# LowLevelv3.net
KiCad netlist of a schematic drawn in EAGLE
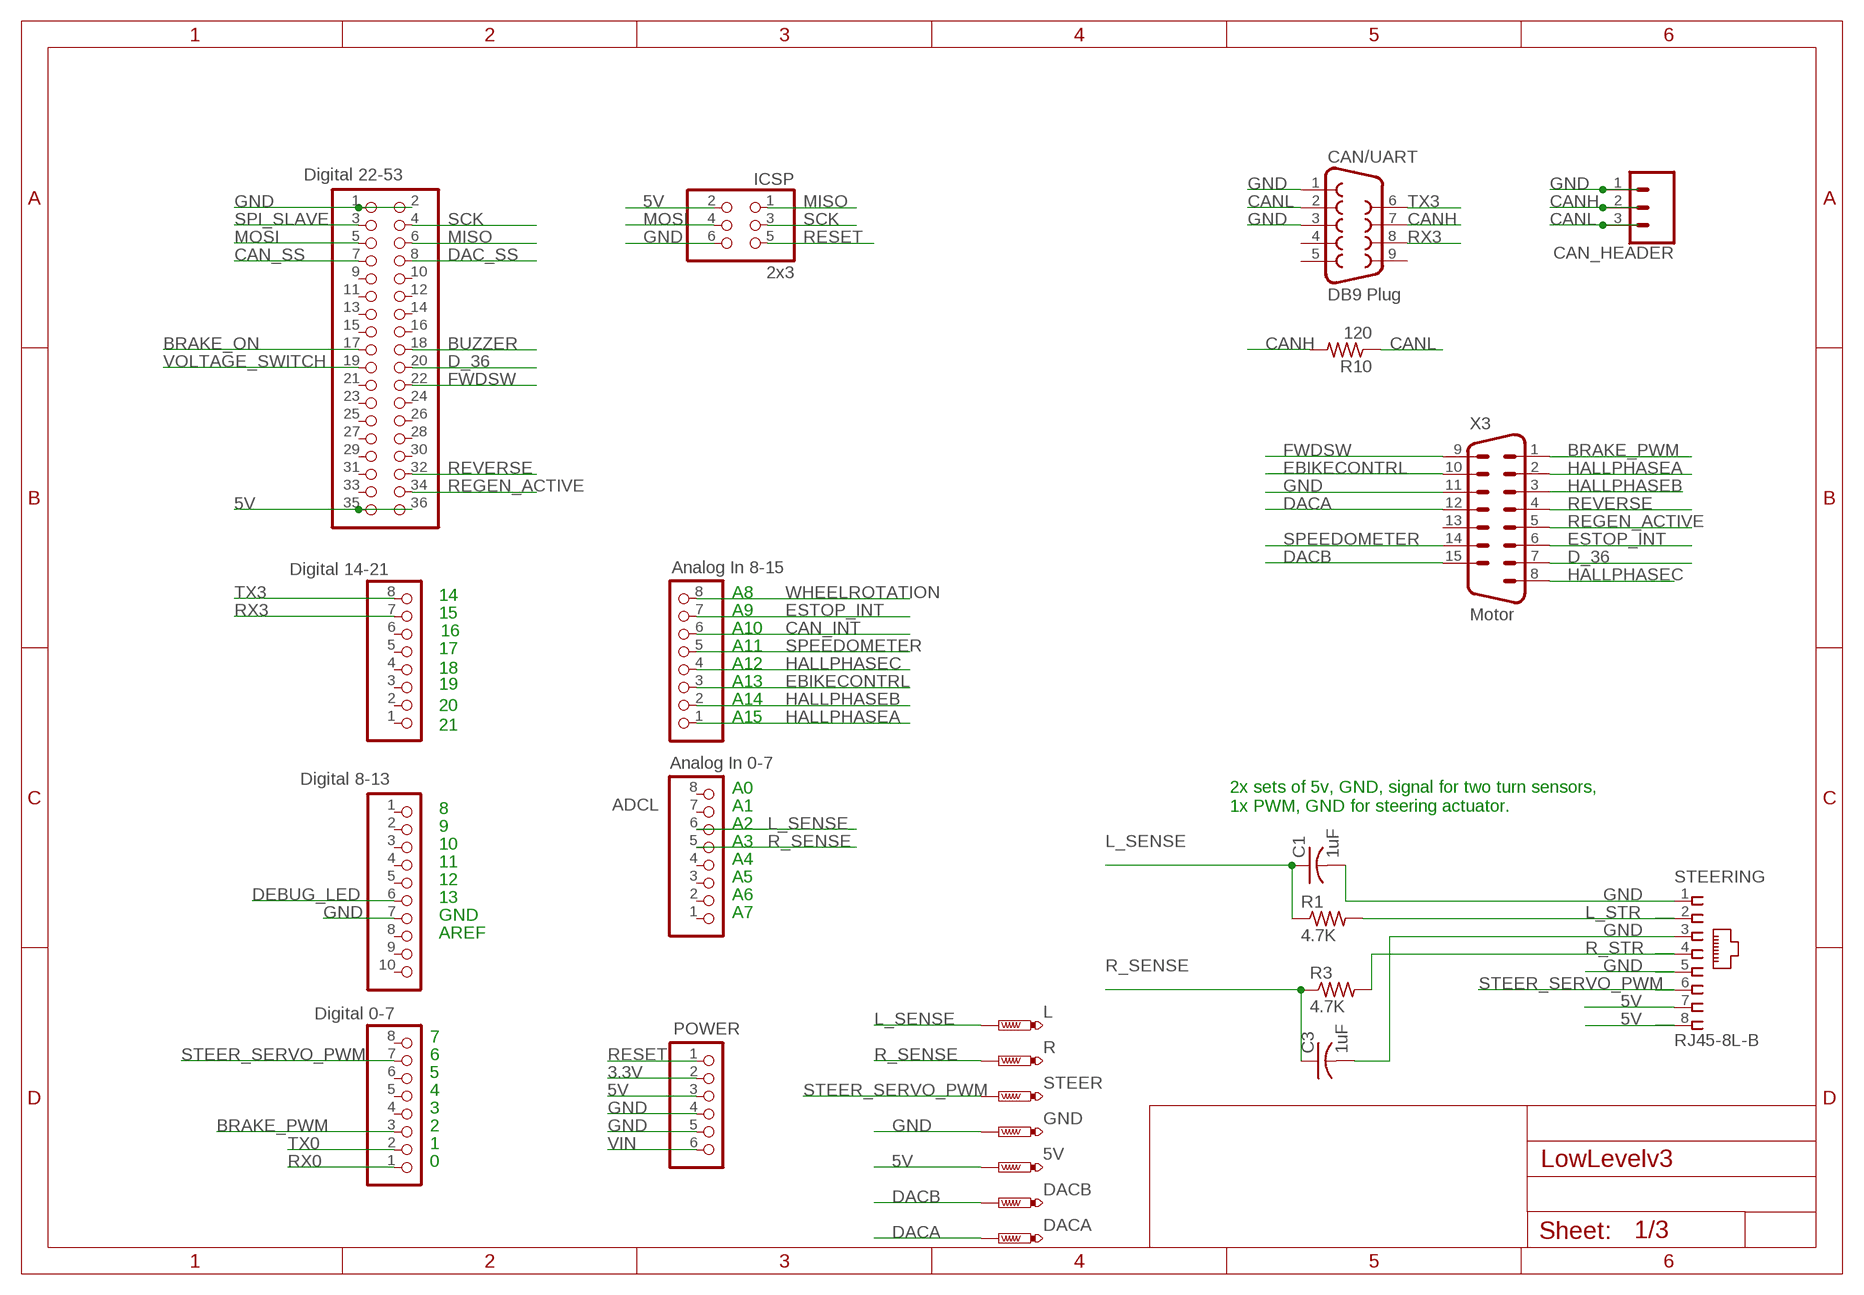
[diagram p0: schematic, sheet 1]
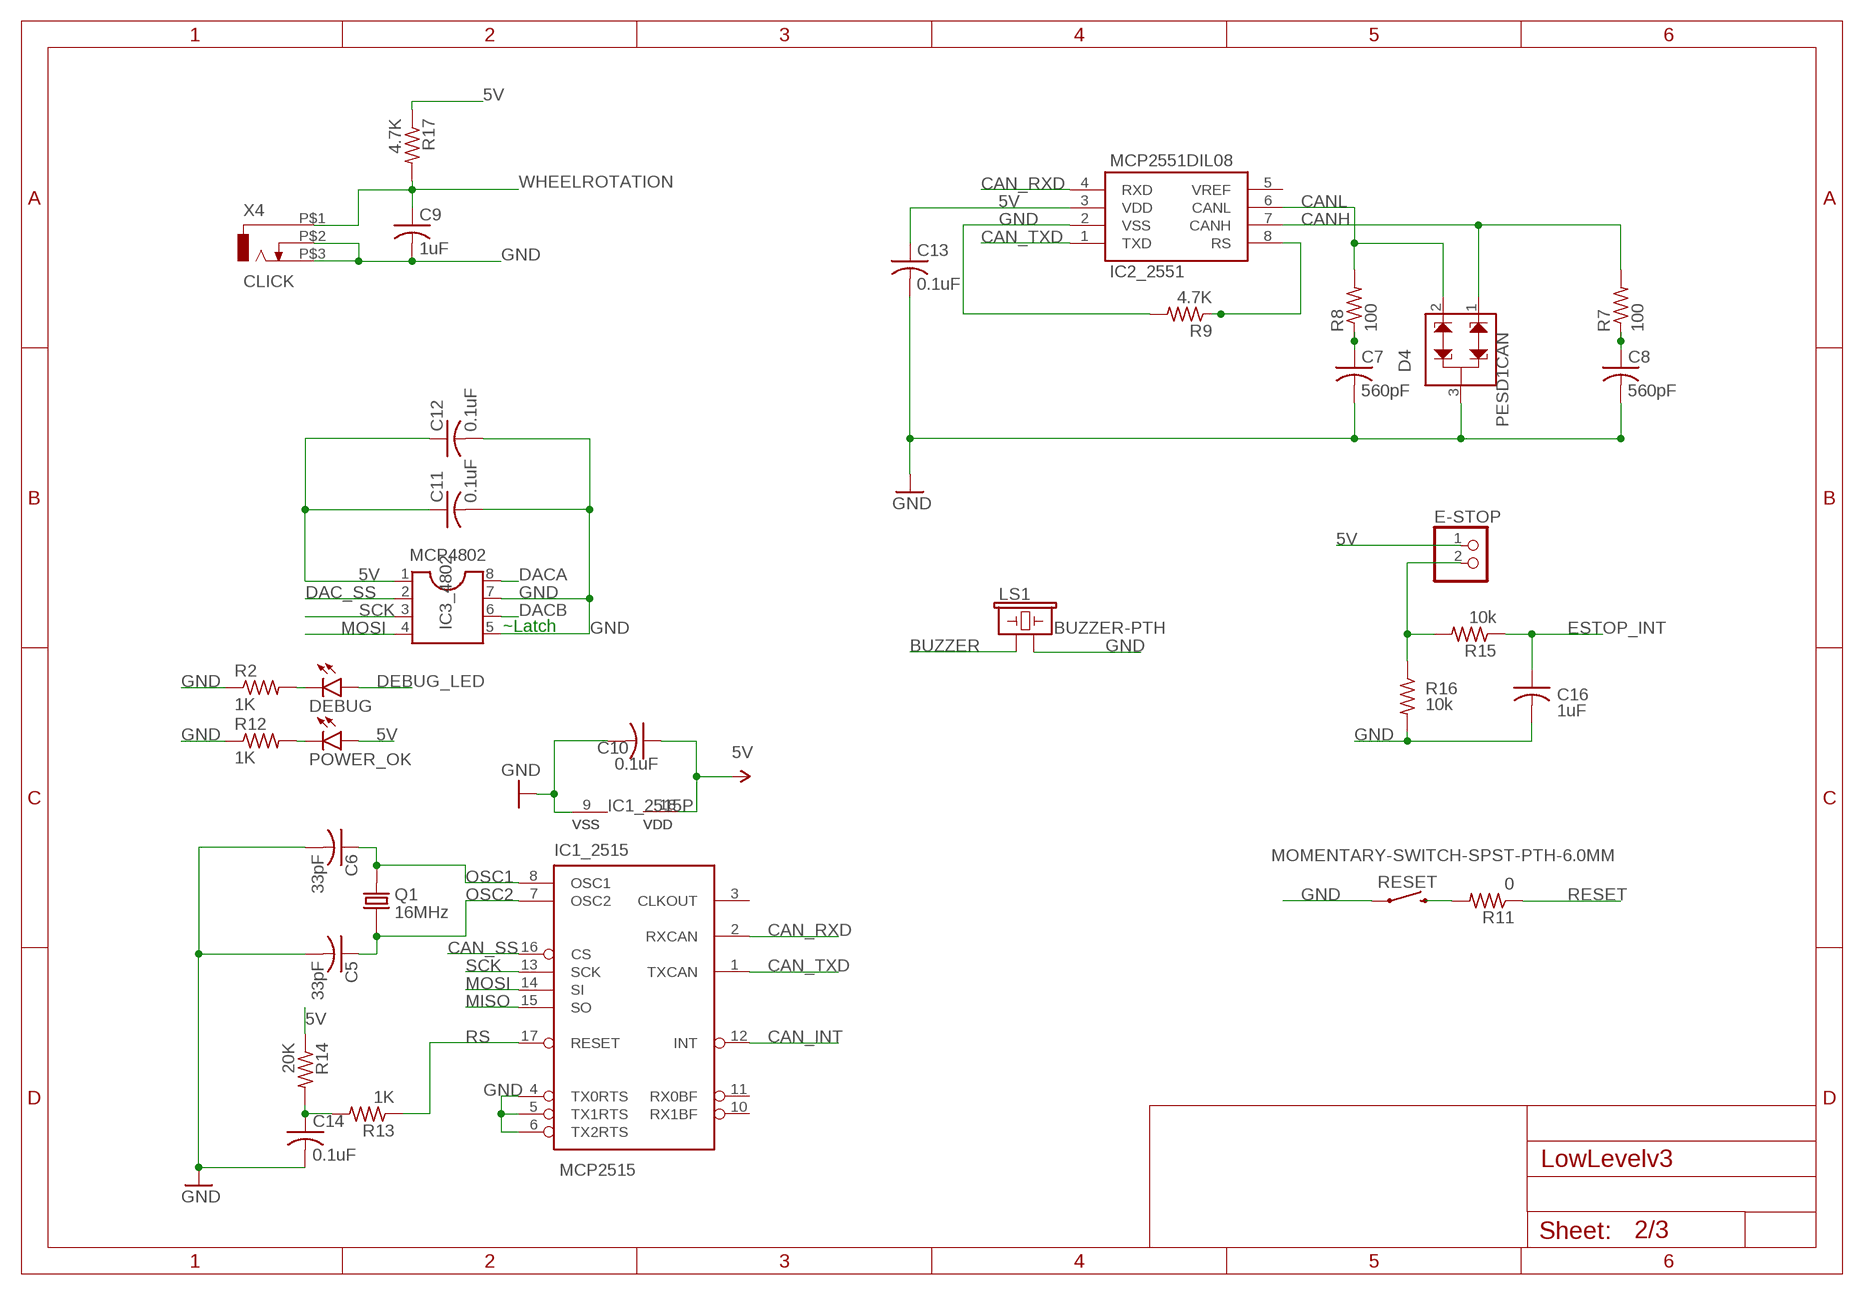
[diagram p1: schematic, sheet 2]
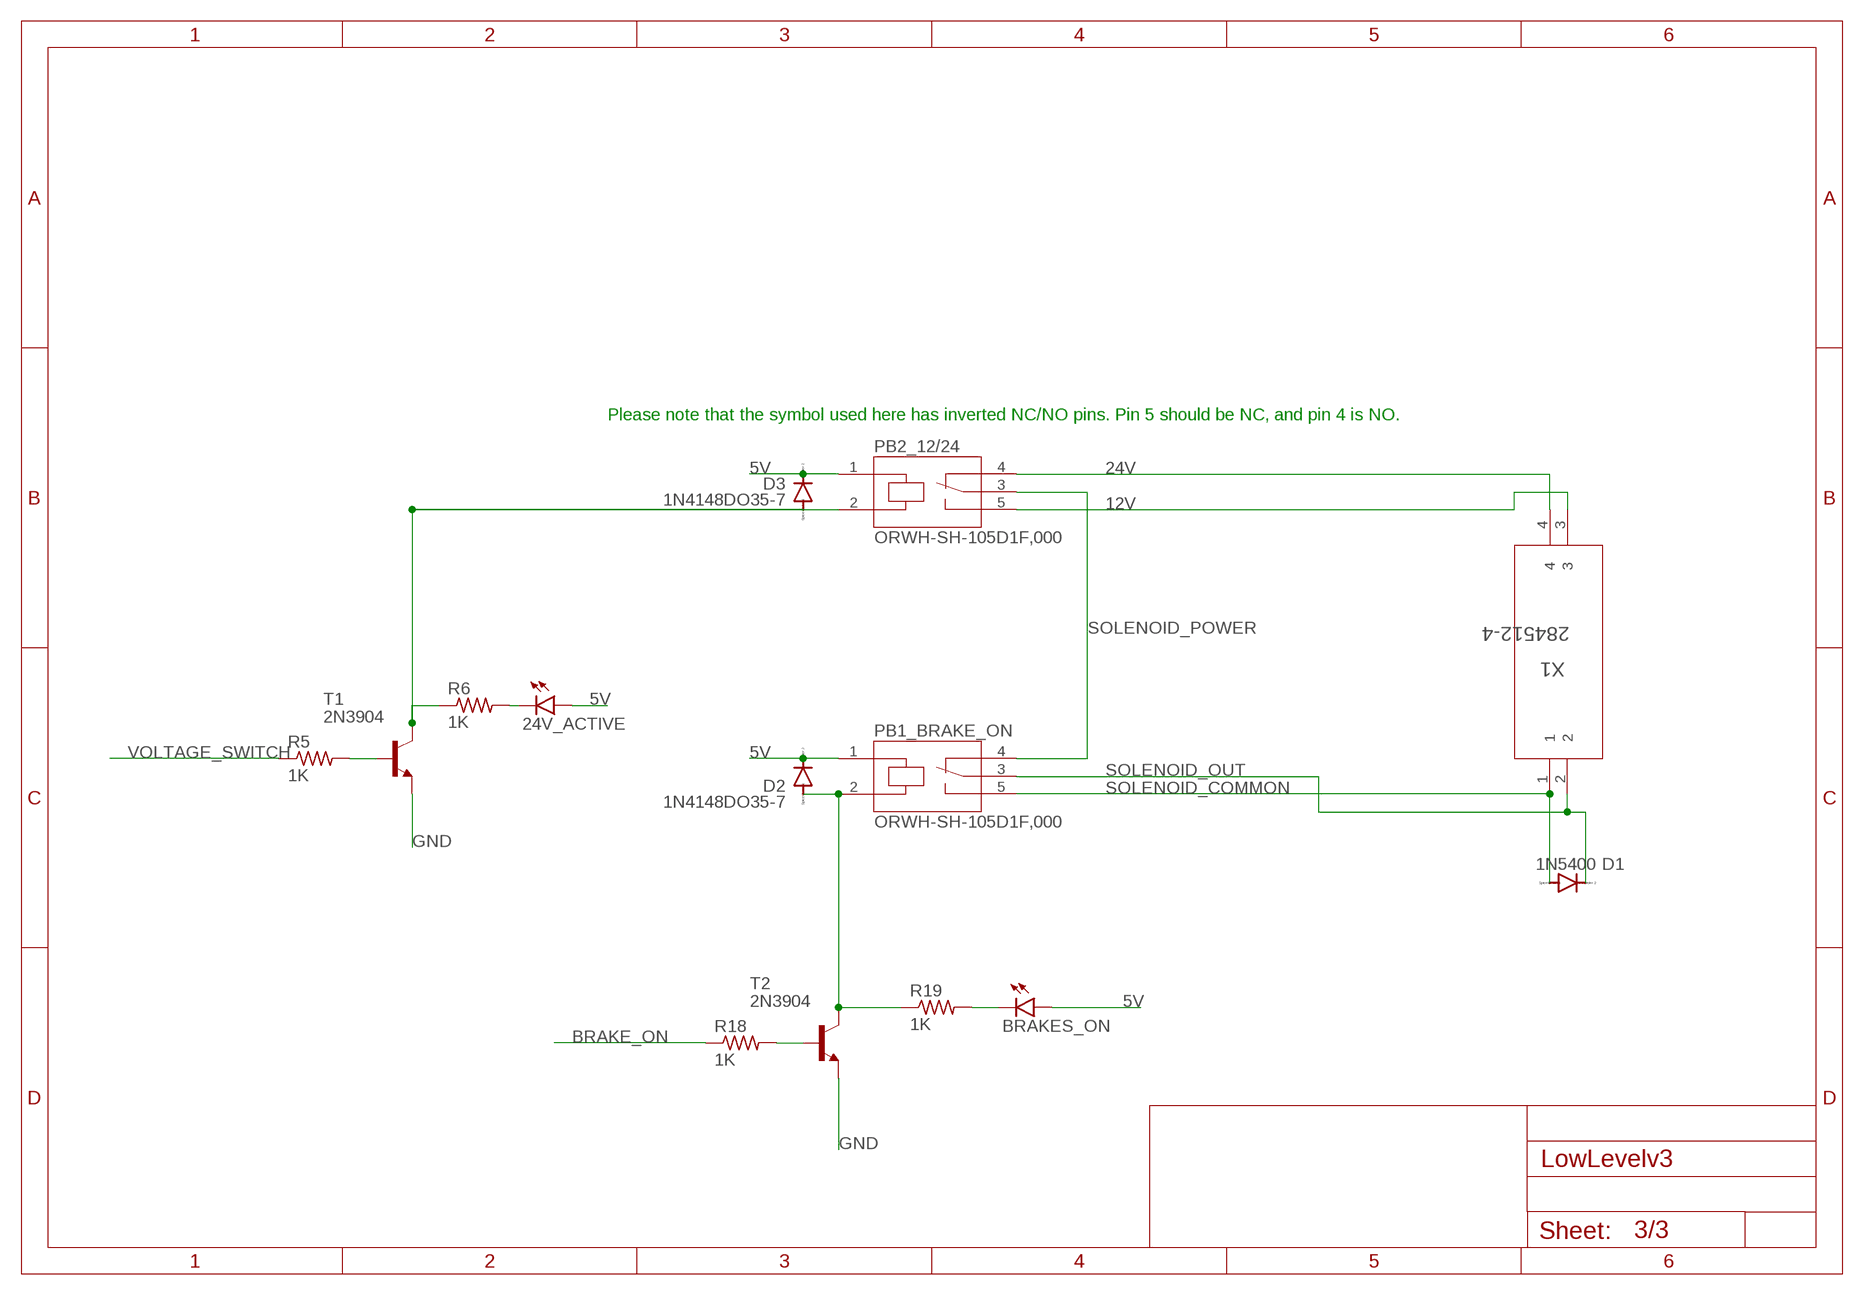
[diagram p2: schematic, sheet 3]

(export (version "E")
  (design (tool "Eeschema 10.0.6"))
  (components
    (comp (ref "5V")
      (value "PTR1PAD1-17")
      (footprint "eagle-import:P1-17")
      (libsource (lib "eagle-import") (part "PTR1PAD1-17"))
    )
    (comp (ref "ADCH")
      (value "Analog In 8-15")
      (footprint "eagle-import:1X08")
      (libsource (lib "eagle-import") (part "PINHD-1X8"))
    )
    (comp (ref "ADCL")
      (value "Analog In 0-7")
      (footprint "eagle-import:1X08")
      (libsource (lib "eagle-import") (part "PINHD-1X8"))
    )
    (comp (ref "C1")
      (value "1uF")
      (footprint "eagle-import:C1206")
      (libsource (lib "eagle-import") (part "C-USC1206"))
    )
    (comp (ref "C3")
      (value "1uF")
      (footprint "eagle-import:C1206")
      (libsource (lib "eagle-import") (part "C-USC1206"))
    )
    (comp (ref "CAN/UART")
      (value "DB9 Plug")
      (footprint "eagle-import:DB9")
      (fields (field (name "SPICEPREFIX") "X"))
      (libsource (lib "eagle-import") (part "DB9FEMALE"))
    )
    (comp (ref "CAN_HEADER")
      (value "CONN_03-SCREW-5MM")
      (footprint "eagle-import:SCREWTERMINAL-5MM-3")
      (libsource (lib "eagle-import") (part "CONN_03-SCREW-5MM"))
    )
    (comp (ref "DACA")
      (value "PTR1PAD1-17")
      (footprint "eagle-import:P1-17")
      (libsource (lib "eagle-import") (part "PTR1PAD1-17"))
    )
    (comp (ref "DACB")
      (value "PTR1PAD1-17")
      (footprint "eagle-import:P1-17")
      (libsource (lib "eagle-import") (part "PTR1PAD1-17"))
    )
    (comp (ref "DIGITAL_0-7")
      (value "Digital 0-7")
      (footprint "eagle-import:1X08")
      (libsource (lib "eagle-import") (part "PINHD-1X8"))
    )
    (comp (ref "DIGITAL_8-13")
      (value "Digital 8-13")
      (footprint "eagle-import:1X10")
      (libsource (lib "eagle-import") (part "PINHD-1X10"))
    )
    (comp (ref "DIGITAL_14-21")
      (value "Digital 14-21")
      (footprint "eagle-import:1X08")
      (libsource (lib "eagle-import") (part "PINHD-1X8"))
    )
    (comp (ref "GND")
      (value "PTR1PAD1-17")
      (footprint "eagle-import:P1-17")
      (libsource (lib "eagle-import") (part "PTR1PAD1-17"))
    )
    (comp (ref "ICSP")
      (value "2x3")
      (footprint "eagle-import:2X03")
      (libsource (lib "eagle-import") (part "PINHD-2X3"))
    )
    (comp (ref "L")
      (value "PTR1PAD1-17")
      (footprint "eagle-import:P1-17")
      (libsource (lib "eagle-import") (part "PTR1PAD1-17"))
    )
    (comp (ref "MEGA_EXPANSION")
      (value "Digital 22-53")
      (footprint "eagle-import:PINHEAD_2X18")
      (libsource (lib "eagle-import") (part "PINHEAD_PINHD-2X18"))
    )
    (comp (ref "POWER")
      (value "PINHD-1X6")
      (footprint "eagle-import:1X06")
      (libsource (lib "eagle-import") (part "PINHD-1X6"))
    )
    (comp (ref "R")
      (value "PTR1PAD1-17")
      (footprint "eagle-import:P1-17")
      (libsource (lib "eagle-import") (part "PTR1PAD1-17"))
    )
    (comp (ref "R1")
      (value "4.7K")
      (footprint "eagle-import:R1206")
      (libsource (lib "eagle-import") (part "R-US_R1206"))
    )
    (comp (ref "R3")
      (value "4.7K")
      (footprint "eagle-import:R1206")
      (libsource (lib "eagle-import") (part "R-US_R1206"))
    )
    (comp (ref "R10")
      (value "120")
      (footprint "eagle-import:R1206")
      (libsource (lib "eagle-import") (part "R-US_R1206"))
    )
    (comp (ref "STEER")
      (value "PTR1PAD1-17")
      (footprint "eagle-import:P1-17")
      (libsource (lib "eagle-import") (part "PTR1PAD1-17"))
    )
    (comp (ref "STEERING")
      (value "RJ45-8L-B")
      (footprint "eagle-import:RJ45-NO-SHIELD")
      (fields (field (name "MF") "TYCO ELECTRONICS"))
      (libsource (lib "eagle-import") (part "RJ45-8L-B"))
    )
    (comp (ref "X3")
      (value "Motor")
      (footprint "eagle-import:182-015-MALE")
      (libsource (lib "eagle-import") (part "M15-182"))
    )
    (comp (ref "24V_ACTIVE")
      (value "LED3MM")
      (footprint "eagle-import:LED3MM")
      (libsource (lib "eagle-import") (part "LED3MM"))
    )
    (comp (ref "BRAKES_ON")
      (value "LED3MM")
      (footprint "eagle-import:LED3MM")
      (libsource (lib "eagle-import") (part "LED3MM"))
    )
    (comp (ref "D1")
      (value "1N5400")
      (footprint "eagle-import:DO201-15")
      (libsource (lib "eagle-import") (part "1N5400"))
    )
    (comp (ref "D2")
      (value "1N4148DO35-7")
      (footprint "eagle-import:DO35-7")
      (libsource (lib "eagle-import") (part "1N4148DO35-7"))
    )
    (comp (ref "D3")
      (value "1N4148DO35-7")
      (footprint "eagle-import:DO35-7")
      (libsource (lib "eagle-import") (part "1N4148DO35-7"))
    )
    (comp (ref "PB1_BRAKE_ON")
      (value "ORWH-SH-105D1F,000")
      (footprint "eagle-import:TE_ORWH-SH-105D1F,000")
      (fields (field (name "DIGI-KEY_PART_NUMBER") "PB2032-ND") (field (name "MF") "TE"))
      (libsource (lib "eagle-import") (part "ORWH-SH-105D1F,000"))
    )
    (comp (ref "PB2_12/24")
      (value "ORWH-SH-105D1F,000")
      (footprint "eagle-import:TE_ORWH-SH-105D1F,000")
      (fields (field (name "DIGI-KEY_PART_NUMBER") "PB2032-ND") (field (name "MF") "TE"))
      (libsource (lib "eagle-import") (part "ORWH-SH-105D1F,000"))
    )
    (comp (ref "R5")
      (value "1K")
      (footprint "eagle-import:R1206")
      (libsource (lib "eagle-import") (part "R-US_R1206"))
    )
    (comp (ref "R6")
      (value "1K")
      (footprint "eagle-import:R1206")
      (libsource (lib "eagle-import") (part "R-US_R1206"))
    )
    (comp (ref "R18")
      (value "1K")
      (footprint "eagle-import:R1206")
      (libsource (lib "eagle-import") (part "R-US_R1206"))
    )
    (comp (ref "R19")
      (value "1K")
      (footprint "eagle-import:R1206")
      (libsource (lib "eagle-import") (part "R-US_R1206"))
    )
    (comp (ref "T1")
      (value "2N3904")
      (footprint "eagle-import:TO92")
      (libsource (lib "eagle-import") (part "2N3904"))
    )
    (comp (ref "T2")
      (value "2N3904")
      (footprint "eagle-import:TO92")
      (libsource (lib "eagle-import") (part "2N3904"))
    )
    (comp (ref "X1")
      (value "284512-4")
      (footprint "eagle-import:284512-4")
      (fields (field (name "MANUFACTURER_PART_NUMBER") "2845124"))
      (libsource (lib "eagle-import") (part "284512-4"))
    )
    (comp (ref "C5")
      (value "33pF")
      (footprint "eagle-import:C1206")
      (libsource (lib "eagle-import") (part "C-USC1206"))
    )
    (comp (ref "C6")
      (value "33pF")
      (footprint "eagle-import:C1206")
      (libsource (lib "eagle-import") (part "C-USC1206"))
    )
    (comp (ref "C7")
      (value "560pF")
      (footprint "eagle-import:C1206")
      (libsource (lib "eagle-import") (part "C-USC1206"))
    )
    (comp (ref "C8")
      (value "560pF")
      (footprint "eagle-import:C1206")
      (libsource (lib "eagle-import") (part "C-USC1206"))
    )
    (comp (ref "C9")
      (value "1uF")
      (footprint "eagle-import:C1206")
      (libsource (lib "eagle-import") (part "C-USC1206"))
    )
    (comp (ref "C10")
      (value "0.1uF")
      (footprint "eagle-import:C1206")
      (libsource (lib "eagle-import") (part "C-USC1206"))
    )
    (comp (ref "C11")
      (value "0.1uF")
      (footprint "eagle-import:C1206")
      (libsource (lib "eagle-import") (part "C-USC1206"))
    )
    (comp (ref "C12")
      (value "0.1uF")
      (footprint "eagle-import:C1206")
      (libsource (lib "eagle-import") (part "C-USC1206"))
    )
    (comp (ref "C13")
      (value "0.1uF")
      (footprint "eagle-import:C1206")
      (libsource (lib "eagle-import") (part "C-USC1206"))
    )
    (comp (ref "C14")
      (value "0.1uF")
      (footprint "eagle-import:C1206")
      (libsource (lib "eagle-import") (part "C-USC1206"))
    )
    (comp (ref "C16")
      (value "1uF")
      (footprint "eagle-import:C1206")
      (libsource (lib "eagle-import") (part "C-USC1206"))
    )
    (comp (ref "D4")
      (value "PESD1CAN")
      (footprint "eagle-import:SPARKFUN-DISCRETESEMI_SOT23-3")
      (fields (field (name "SPICEPREFIX") "J"))
      (libsource (lib "eagle-import") (part "PESD1CAN"))
    )
    (comp (ref "DEBUG")
      (value "LED3MM")
      (footprint "eagle-import:LED3MM")
      (libsource (lib "eagle-import") (part "LED3MM"))
    )
    (comp (ref "E-STOP")
      (value "PINHD-1X2")
      (footprint "eagle-import:1X02")
      (libsource (lib "eagle-import") (part "PINHD-1X2"))
    )
    (comp (ref "IC1_2515")
      (value "MCP2515")
      (footprint "eagle-import:DIP18")
      (fields (field (name "SPICEPREFIX") "X"))
      (libsource (lib "eagle-import") (part "MCP2515(MCP2510)P"))
    )
    (comp (ref "IC2_2551")
      (value "MCP2551DIL08")
      (footprint "eagle-import:IC-PACKAGE_DIL08")
      (fields (field (name "SPICEPREFIX") "X"))
      (libsource (lib "eagle-import") (part "MCP2551DIL08"))
    )
    (comp (ref "IC3_4802")
      (value "MCP4802")
      (footprint "eagle-import:DIL08")
      (libsource (lib "eagle-import") (part "DIL8"))
    )
    (comp (ref "LS1")
      (value "BUZZER-PTH")
      (footprint "eagle-import:BUZZER-12MM")
      (libsource (lib "eagle-import") (part "BUZZER-PTH"))
    )
    (comp (ref "POWER_OK")
      (value "LED3MM")
      (footprint "eagle-import:LED3MM")
      (libsource (lib "eagle-import") (part "LED3MM"))
    )
    (comp (ref "Q1")
      (value "16MHz")
      (footprint "eagle-import:XTAL_ECS-160-20-46X")
      (fields
        (field (name "DIGI-KEY_PART_NUMBER") "XC1759-ND")
        (field (name "MF") "ECS Inc.")
        (field (name "MP") "ECS-160-20-46X")
        (field (name "SPICEPREFIX") "B")
      )
      (libsource (lib "eagle-import") (part "ECS-160-20-46X"))
    )
    (comp (ref "R2")
      (value "1K")
      (footprint "eagle-import:R1206")
      (libsource (lib "eagle-import") (part "R-US_R1206"))
    )
    (comp (ref "R7")
      (value "100")
      (footprint "eagle-import:R1206")
      (libsource (lib "eagle-import") (part "R-US_R1206"))
    )
    (comp (ref "R8")
      (value "100")
      (footprint "eagle-import:R1206")
      (libsource (lib "eagle-import") (part "R-US_R1206"))
    )
    (comp (ref "R9")
      (value "4.7K")
      (footprint "eagle-import:R1206")
      (libsource (lib "eagle-import") (part "R-US_R1206"))
    )
    (comp (ref "R11")
      (value "0")
      (footprint "eagle-import:R1206")
      (libsource (lib "eagle-import") (part "R-US_R1206"))
    )
    (comp (ref "R12")
      (value "1K")
      (footprint "eagle-import:R1206")
      (libsource (lib "eagle-import") (part "R-US_R1206"))
    )
    (comp (ref "R13")
      (value "1K")
      (footprint "eagle-import:R1206")
      (libsource (lib "eagle-import") (part "R-US_R1206"))
    )
    (comp (ref "R14")
      (value "20K")
      (footprint "eagle-import:R1206")
      (libsource (lib "eagle-import") (part "R-US_R1206"))
    )
    (comp (ref "R15")
      (value "10k")
      (footprint "eagle-import:R1206")
      (libsource (lib "eagle-import") (part "R-US_R1206"))
    )
    (comp (ref "R16")
      (value "10k")
      (footprint "eagle-import:R1206")
      (libsource (lib "eagle-import") (part "R-US_R1206"))
    )
    (comp (ref "R17")
      (value "4.7K")
      (footprint "eagle-import:R1206")
      (libsource (lib "eagle-import") (part "R-US_R1206"))
    )
    (comp (ref "RESET")
      (value "MOMENTARY-SWITCH-SPST-PTH-6.0MM")
      (footprint "eagle-import:TACTILE_SWITCH_PTH_6.0MM")
      (libsource (lib "eagle-import") (part "MOMENTARY-SWITCH-SPST-PTH-6.0MM"))
    )
    (comp (ref "X4")
      (value "CLICK")
      (footprint "eagle-import:ODO_JACK")
      (libsource (lib "eagle-import") (part "ODO_JACK"))
    )
  )
  (nets
    (net (code "1") (name "3.3V") (class "Default")
      (node (ref "POWER") (pin "2") (pinfunction "2_2") (pintype "passive"))
    )
    (net (code "2") (name "5V") (class "Default")
      (node (ref "24V_ACTIVE") (pin "A") (pinfunction "A_A") (pintype "passive"))
      (node (ref "5V") (pin "TP") (pinfunction "TP_TP") (pintype "input"))
      (node (ref "BRAKES_ON") (pin "A") (pinfunction "A_A") (pintype "passive"))
      (node (ref "C10") (pin "1") (pinfunction "1_1") (pintype "passive"))
      (node (ref "C11") (pin "1") (pinfunction "1_1") (pintype "passive"))
      (node (ref "C12") (pin "1") (pinfunction "1_1") (pintype "passive"))
      (node (ref "C13") (pin "1") (pinfunction "1_1") (pintype "passive"))
      (node (ref "D2") (pin "C") (pinfunction "C_C") (pintype "passive"))
      (node (ref "D3") (pin "C") (pinfunction "C_C") (pintype "passive"))
      (node (ref "E-STOP") (pin "1") (pinfunction "1_1") (pintype "passive"))
      (node (ref "IC1_2515") (pin "18") (pinfunction "VDD_18") (pintype "power_in"))
      (node (ref "IC2_2551") (pin "3") (pinfunction "VDD_3") (pintype "bidirectional"))
      (node (ref "IC3_4802") (pin "1") (pinfunction "1_1") (pintype "passive"))
      (node (ref "ICSP") (pin "2") (pinfunction "2_2") (pintype "passive"))
      (node (ref "MEGA_EXPANSION") (pin "35") (pinfunction "35_35") (pintype "passive"))
      (node (ref "MEGA_EXPANSION") (pin "36") (pinfunction "36_36") (pintype "passive"))
      (node (ref "PB1_BRAKE_ON") (pin "1") (pinfunction "C1_1") (pintype "passive"))
      (node (ref "PB2_12/24") (pin "1") (pinfunction "C1_1") (pintype "passive"))
      (node (ref "POWER") (pin "3") (pinfunction "3_3") (pintype "passive"))
      (node (ref "POWER_OK") (pin "A") (pinfunction "A_A") (pintype "passive"))
      (node (ref "R14") (pin "1") (pinfunction "1_1") (pintype "passive"))
      (node (ref "R17") (pin "1") (pinfunction "1_1") (pintype "passive"))
      (node (ref "STEERING") (pin "7") (pinfunction "7_7") (pintype "passive"))
      (node (ref "STEERING") (pin "8") (pinfunction "8_8") (pintype "passive"))
    )
    (net (code "3") (name "12V") (class "Default")
      (node (ref "PB2_12/24") (pin "5") (pinfunction "NO_5") (pintype "passive"))
      (node (ref "X1") (pin "3") (pinfunction "3_3") (pintype "passive"))
    )
    (net (code "4") (name "24V") (class "Default")
      (node (ref "PB2_12/24") (pin "4") (pinfunction "NC_4") (pintype "passive"))
      (node (ref "X1") (pin "4") (pinfunction "4_4") (pintype "passive"))
    )
    (net (code "5") (name "BRAKE_ON") (class "Default")
      (node (ref "MEGA_EXPANSION") (pin "17") (pinfunction "17_17") (pintype "passive"))
      (node (ref "R18") (pin "1") (pinfunction "1_1") (pintype "passive"))
    )
    (net (code "6") (name "BRAKE_PWM") (class "Default")
      (node (ref "DIGITAL_0-7") (pin "3") (pinfunction "3_3") (pintype "passive"))
      (node (ref "X3") (pin "1") (pinfunction "1_1") (pintype "passive"))
    )
    (net (code "7") (name "BUZZER") (class "Default")
      (node (ref "LS1") (pin "+") (pinfunction "1_+") (pintype "passive"))
      (node (ref "MEGA_EXPANSION") (pin "18") (pinfunction "18_18") (pintype "passive"))
    )
    (net (code "8") (name "CANH") (class "Default")
      (node (ref "CAN/UART") (pin "7") (pinfunction "7_7") (pintype "passive"))
      (node (ref "CAN_HEADER") (pin "2") (pinfunction "2_2") (pintype "passive"))
      (node (ref "D4") (pin "1") (pinfunction "1_1") (pintype "bidirectional"))
      (node (ref "IC2_2551") (pin "7") (pinfunction "CANH_7") (pintype "bidirectional"))
      (node (ref "R10") (pin "2") (pinfunction "2_2") (pintype "passive"))
      (node (ref "R7") (pin "2") (pinfunction "2_2") (pintype "passive"))
    )
    (net (code "9") (name "CANL") (class "Default")
      (node (ref "CAN/UART") (pin "2") (pinfunction "2_2") (pintype "passive"))
      (node (ref "CAN_HEADER") (pin "3") (pinfunction "3_3") (pintype "passive"))
      (node (ref "D4") (pin "2") (pinfunction "2_2") (pintype "bidirectional"))
      (node (ref "IC2_2551") (pin "6") (pinfunction "CANL_6") (pintype "bidirectional"))
      (node (ref "R10") (pin "1") (pinfunction "1_1") (pintype "passive"))
      (node (ref "R8") (pin "2") (pinfunction "2_2") (pintype "passive"))
    )
    (net (code "10") (name "CAN_INT") (class "Default")
      (node (ref "ADCH") (pin "6") (pinfunction "6_6") (pintype "passive"))
      (node (ref "IC1_2515") (pin "12") (pinfunction "INT_12") (pintype "output"))
    )
    (net (code "11") (name "CAN_RXD") (class "Default")
      (node (ref "IC1_2515") (pin "2") (pinfunction "RXCAN_2") (pintype "input"))
      (node (ref "IC2_2551") (pin "4") (pinfunction "RXD_4") (pintype "bidirectional"))
    )
    (net (code "12") (name "CAN_SS") (class "Default")
      (node (ref "IC1_2515") (pin "16") (pinfunction "CS_16") (pintype "input"))
      (node (ref "MEGA_EXPANSION") (pin "7") (pinfunction "7_7") (pintype "passive"))
    )
    (net (code "13") (name "CAN_TXD") (class "Default")
      (node (ref "IC1_2515") (pin "1") (pinfunction "TXCAN_1") (pintype "output"))
      (node (ref "IC2_2551") (pin "1") (pinfunction "TXD_1") (pintype "bidirectional"))
    )
    (net (code "14") (name "DACA") (class "Default")
      (node (ref "DACA") (pin "TP") (pinfunction "TP_TP") (pintype "input"))
      (node (ref "IC3_4802") (pin "8") (pinfunction "8_8") (pintype "passive"))
      (node (ref "X3") (pin "12") (pinfunction "12_12") (pintype "passive"))
    )
    (net (code "15") (name "DACB") (class "Default")
      (node (ref "DACB") (pin "TP") (pinfunction "TP_TP") (pintype "input"))
      (node (ref "IC3_4802") (pin "6") (pinfunction "6_6") (pintype "passive"))
      (node (ref "X3") (pin "15") (pinfunction "15_15") (pintype "passive"))
    )
    (net (code "16") (name "DAC_SS") (class "Default")
      (node (ref "IC3_4802") (pin "2") (pinfunction "2_2") (pintype "passive"))
      (node (ref "MEGA_EXPANSION") (pin "8") (pinfunction "8_8") (pintype "passive"))
    )
    (net (code "17") (name "DEBUG_LED") (class "Default")
      (node (ref "DEBUG") (pin "A") (pinfunction "A_A") (pintype "passive"))
      (node (ref "DIGITAL_8-13") (pin "6") (pinfunction "6_6") (pintype "passive"))
    )
    (net (code "18") (name "D_36") (class "Default")
      (node (ref "MEGA_EXPANSION") (pin "20") (pinfunction "20_20") (pintype "passive"))
      (node (ref "X3") (pin "7") (pinfunction "7_7") (pintype "passive"))
    )
    (net (code "19") (name "EBIKECONTRL") (class "Default")
      (node (ref "ADCH") (pin "3") (pinfunction "3_3") (pintype "passive"))
      (node (ref "X3") (pin "10") (pinfunction "10_10") (pintype "passive"))
    )
    (net (code "20") (name "ESTOP_INT") (class "Default")
      (node (ref "ADCH") (pin "7") (pinfunction "7_7") (pintype "passive"))
      (node (ref "C16") (pin "1") (pinfunction "1_1") (pintype "passive"))
      (node (ref "R15") (pin "1") (pinfunction "1_1") (pintype "passive"))
      (node (ref "X3") (pin "6") (pinfunction "6_6") (pintype "passive"))
    )
    (net (code "21") (name "FWDSW") (class "Default")
      (node (ref "MEGA_EXPANSION") (pin "22") (pinfunction "22_22") (pintype "passive"))
      (node (ref "X3") (pin "9") (pinfunction "9_9") (pintype "passive"))
    )
    (net (code "22") (name "GND") (class "Default")
      (node (ref "C1") (pin "2") (pinfunction "2_2") (pintype "passive"))
      (node (ref "C10") (pin "2") (pinfunction "2_2") (pintype "passive"))
      (node (ref "C11") (pin "2") (pinfunction "2_2") (pintype "passive"))
      (node (ref "C12") (pin "2") (pinfunction "2_2") (pintype "passive"))
      (node (ref "C13") (pin "2") (pinfunction "2_2") (pintype "passive"))
      (node (ref "C14") (pin "2") (pinfunction "2_2") (pintype "passive"))
      (node (ref "C16") (pin "2") (pinfunction "2_2") (pintype "passive"))
      (node (ref "C3") (pin "2") (pinfunction "2_2") (pintype "passive"))
      (node (ref "C5") (pin "2") (pinfunction "2_2") (pintype "passive"))
      (node (ref "C6") (pin "2") (pinfunction "2_2") (pintype "passive"))
      (node (ref "C7") (pin "2") (pinfunction "2_2") (pintype "passive"))
      (node (ref "C8") (pin "2") (pinfunction "2_2") (pintype "passive"))
      (node (ref "C9") (pin "2") (pinfunction "2_2") (pintype "passive"))
      (node (ref "CAN/UART") (pin "1") (pinfunction "1_1") (pintype "passive"))
      (node (ref "CAN/UART") (pin "3") (pinfunction "3_3") (pintype "passive"))
      (node (ref "CAN_HEADER") (pin "1") (pinfunction "1_1") (pintype "passive"))
      (node (ref "D4") (pin "3") (pinfunction "3_3") (pintype "bidirectional"))
      (node (ref "DIGITAL_8-13") (pin "7") (pinfunction "7_7") (pintype "passive"))
      (node (ref "GND") (pin "TP") (pinfunction "TP_TP") (pintype "input"))
      (node (ref "IC1_2515") (pin "4") (pinfunction "TX0RTS_4") (pintype "input"))
      (node (ref "IC1_2515") (pin "5") (pinfunction "TX1RTS_5") (pintype "input"))
      (node (ref "IC1_2515") (pin "6") (pinfunction "TX2RTS_6") (pintype "input"))
      (node (ref "IC1_2515") (pin "9") (pinfunction "VSS_9") (pintype "power_in"))
      (node (ref "IC2_2551") (pin "2") (pinfunction "VSS_2") (pintype "bidirectional"))
      (node (ref "IC3_4802") (pin "5") (pinfunction "5_5") (pintype "passive"))
      (node (ref "IC3_4802") (pin "7") (pinfunction "7_7") (pintype "passive"))
      (node (ref "ICSP") (pin "6") (pinfunction "6_6") (pintype "passive"))
      (node (ref "LS1") (pin "-") (pinfunction "2_-") (pintype "passive"))
      (node (ref "MEGA_EXPANSION") (pin "1") (pinfunction "1_1") (pintype "passive"))
      (node (ref "MEGA_EXPANSION") (pin "2") (pinfunction "2_2") (pintype "passive"))
      (node (ref "POWER") (pin "4") (pinfunction "4_4") (pintype "passive"))
      (node (ref "POWER") (pin "5") (pinfunction "5_5") (pintype "passive"))
      (node (ref "R12") (pin "1") (pinfunction "1_1") (pintype "passive"))
      (node (ref "R16") (pin "2") (pinfunction "2_2") (pintype "passive"))
      (node (ref "R2") (pin "1") (pinfunction "1_1") (pintype "passive"))
      (node (ref "R9") (pin "2") (pinfunction "2_2") (pintype "passive"))
      (node (ref "RESET") (pin "1") (pinfunction "1_1") (pintype "passive"))
      (node (ref "STEERING") (pin "1") (pinfunction "1_1") (pintype "passive"))
      (node (ref "STEERING") (pin "3") (pinfunction "3_3") (pintype "passive"))
      (node (ref "STEERING") (pin "5") (pinfunction "5_5") (pintype "passive"))
      (node (ref "T1") (pin "3") (pinfunction "E_3") (pintype "passive"))
      (node (ref "T2") (pin "3") (pinfunction "E_3") (pintype "passive"))
      (node (ref "X3") (pin "11") (pinfunction "11_11") (pintype "passive"))
      (node (ref "X4") (pin "P$2") (pinfunction "2_P$2") (pintype "passive"))
      (node (ref "X4") (pin "P$3") (pinfunction "3_P$3") (pintype "passive"))
    )
    (net (code "23") (name "HALLPHASEA") (class "Default")
      (node (ref "ADCH") (pin "1") (pinfunction "1_1") (pintype "passive"))
      (node (ref "X3") (pin "2") (pinfunction "2_2") (pintype "passive"))
    )
    (net (code "24") (name "HALLPHASEB") (class "Default")
      (node (ref "ADCH") (pin "2") (pinfunction "2_2") (pintype "passive"))
      (node (ref "X3") (pin "3") (pinfunction "3_3") (pintype "passive"))
    )
    (net (code "25") (name "HALLPHASEC") (class "Default")
      (node (ref "ADCH") (pin "4") (pinfunction "4_4") (pintype "passive"))
      (node (ref "X3") (pin "8") (pinfunction "8_8") (pintype "passive"))
    )
    (net (code "26") (name "L_SENSE") (class "Default")
      (node (ref "ADCL") (pin "6") (pinfunction "6_6") (pintype "passive"))
      (node (ref "C1") (pin "1") (pinfunction "1_1") (pintype "passive"))
      (node (ref "L") (pin "TP") (pinfunction "TP_TP") (pintype "input"))
      (node (ref "R1") (pin "1") (pinfunction "1_1") (pintype "passive"))
    )
    (net (code "27") (name "L_STR") (class "Default")
      (node (ref "R1") (pin "2") (pinfunction "2_2") (pintype "passive"))
      (node (ref "STEERING") (pin "2") (pinfunction "2_2") (pintype "passive"))
    )
    (net (code "28") (name "MISO") (class "Default")
      (node (ref "IC1_2515") (pin "15") (pinfunction "SO_15") (pintype "output"))
      (node (ref "ICSP") (pin "1") (pinfunction "1_1") (pintype "passive"))
      (node (ref "MEGA_EXPANSION") (pin "6") (pinfunction "6_6") (pintype "passive"))
    )
    (net (code "29") (name "MOSI") (class "Default")
      (node (ref "IC1_2515") (pin "14") (pinfunction "SI_14") (pintype "input"))
      (node (ref "IC3_4802") (pin "4") (pinfunction "4_4") (pintype "passive"))
      (node (ref "ICSP") (pin "4") (pinfunction "4_4") (pintype "passive"))
      (node (ref "MEGA_EXPANSION") (pin "5") (pinfunction "5_5") (pintype "passive"))
    )
    (net (code "30") (name "Net-(24V_ACTIVE-C)") (class "Default")
      (node (ref "24V_ACTIVE") (pin "K") (pinfunction "C_K") (pintype "passive"))
      (node (ref "R6") (pin "2") (pinfunction "2_2") (pintype "passive"))
    )
    (net (code "31") (name "Net-(BRAKES_ON-C)") (class "Default")
      (node (ref "BRAKES_ON") (pin "K") (pinfunction "C_K") (pintype "passive"))
      (node (ref "R19") (pin "2") (pinfunction "2_2") (pintype "passive"))
    )
    (net (code "32") (name "Net-(C7-Pad1)") (class "Default")
      (node (ref "C7") (pin "1") (pinfunction "1_1") (pintype "passive"))
      (node (ref "R8") (pin "1") (pinfunction "1_1") (pintype "passive"))
    )
    (net (code "33") (name "Net-(C8-Pad1)") (class "Default")
      (node (ref "C8") (pin "1") (pinfunction "1_1") (pintype "passive"))
      (node (ref "R7") (pin "1") (pinfunction "1_1") (pintype "passive"))
    )
    (net (code "34") (name "Net-(C14-Pad1)") (class "Default")
      (node (ref "C14") (pin "1") (pinfunction "1_1") (pintype "passive"))
      (node (ref "R13") (pin "2") (pinfunction "2_2") (pintype "passive"))
      (node (ref "R14") (pin "2") (pinfunction "2_2") (pintype "passive"))
    )
    (net (code "35") (name "Net-(DEBUG-C)") (class "Default")
      (node (ref "DEBUG") (pin "K") (pinfunction "C_K") (pintype "passive"))
      (node (ref "R2") (pin "2") (pinfunction "2_2") (pintype "passive"))
    )
    (net (code "36") (name "Net-(E-STOP-Pad2)") (class "Default")
      (node (ref "E-STOP") (pin "2") (pinfunction "2_2") (pintype "passive"))
      (node (ref "R15") (pin "2") (pinfunction "2_2") (pintype "passive"))
      (node (ref "R16") (pin "1") (pinfunction "1_1") (pintype "passive"))
    )
    (net (code "37") (name "Net-(IC2_2551-RS)") (class "Default")
      (node (ref "IC2_2551") (pin "8") (pinfunction "RS_8") (pintype "bidirectional"))
      (node (ref "R9") (pin "1") (pinfunction "1_1") (pintype "passive"))
    )
    (net (code "38") (name "Net-(PB1_BRAKE_ON-C2)") (class "Default")
      (node (ref "D2") (pin "A") (pinfunction "A_A") (pintype "passive"))
      (node (ref "PB1_BRAKE_ON") (pin "2") (pinfunction "C2_2") (pintype "passive"))
      (node (ref "R19") (pin "1") (pinfunction "1_1") (pintype "passive"))
      (node (ref "T2") (pin "1") (pinfunction "C_1") (pintype "passive"))
    )
    (net (code "39") (name "Net-(PB2_12/24-C2)") (class "Default")
      (node (ref "D3") (pin "A") (pinfunction "A_A") (pintype "passive"))
      (node (ref "PB2_12/24") (pin "2") (pinfunction "C2_2") (pintype "passive"))
      (node (ref "R6") (pin "1") (pinfunction "1_1") (pintype "passive"))
      (node (ref "T1") (pin "1") (pinfunction "C_1") (pintype "passive"))
    )
    (net (code "40") (name "Net-(POWER_OK-C)") (class "Default")
      (node (ref "POWER_OK") (pin "K") (pinfunction "C_K") (pintype "passive"))
      (node (ref "R12") (pin "2") (pinfunction "2_2") (pintype "passive"))
    )
    (net (code "41") (name "Net-(RESET-2)") (class "Default")
      (node (ref "R11") (pin "2") (pinfunction "2_2") (pintype "passive"))
      (node (ref "RESET") (pin "3") (pinfunction "2_3") (pintype "passive"))
    )
    (net (code "42") (name "Net-(T1-B)") (class "Default")
      (node (ref "R5") (pin "2") (pinfunction "2_2") (pintype "passive"))
      (node (ref "T1") (pin "2") (pinfunction "B_2") (pintype "passive"))
    )
    (net (code "43") (name "Net-(T2-B)") (class "Default")
      (node (ref "R18") (pin "2") (pinfunction "2_2") (pintype "passive"))
      (node (ref "T2") (pin "2") (pinfunction "B_2") (pintype "passive"))
    )
    (net (code "44") (name "OSC1") (class "Default")
      (node (ref "C6") (pin "1") (pinfunction "1_1") (pintype "passive"))
      (node (ref "IC1_2515") (pin "8") (pinfunction "OSC1_8") (pintype "input"))
      (node (ref "Q1") (pin "2") (pinfunction "2_2") (pintype "passive"))
    )
    (net (code "45") (name "OSC2") (class "Default")
      (node (ref "C5") (pin "1") (pinfunction "1_1") (pintype "passive"))
      (node (ref "IC1_2515") (pin "7") (pinfunction "OSC2_7") (pintype "output"))
      (node (ref "Q1") (pin "1") (pinfunction "1_1") (pintype "passive"))
    )
    (net (code "46") (name "REGEN_ACTIVE") (class "Default")
      (node (ref "MEGA_EXPANSION") (pin "34") (pinfunction "34_34") (pintype "passive"))
      (node (ref "X3") (pin "5") (pinfunction "5_5") (pintype "passive"))
    )
    (net (code "47") (name "RESET") (class "Default")
      (node (ref "ICSP") (pin "5") (pinfunction "5_5") (pintype "passive"))
      (node (ref "POWER") (pin "1") (pinfunction "1_1") (pintype "passive"))
      (node (ref "R11") (pin "1") (pinfunction "1_1") (pintype "passive"))
    )
    (net (code "48") (name "REVERSE") (class "Default")
      (node (ref "MEGA_EXPANSION") (pin "32") (pinfunction "32_32") (pintype "passive"))
      (node (ref "X3") (pin "4") (pinfunction "4_4") (pintype "passive"))
    )
    (net (code "49") (name "RS") (class "Default")
      (node (ref "IC1_2515") (pin "17") (pinfunction "RESET_17") (pintype "input"))
      (node (ref "R13") (pin "1") (pinfunction "1_1") (pintype "passive"))
    )
    (net (code "50") (name "RX0") (class "Default")
      (node (ref "DIGITAL_0-7") (pin "1") (pinfunction "1_1") (pintype "passive"))
    )
    (net (code "51") (name "RX3") (class "Default")
      (node (ref "CAN/UART") (pin "8") (pinfunction "8_8") (pintype "passive"))
      (node (ref "DIGITAL_14-21") (pin "7") (pinfunction "7_7") (pintype "passive"))
    )
    (net (code "52") (name "R_SENSE") (class "Default")
      (node (ref "ADCL") (pin "5") (pinfunction "5_5") (pintype "passive"))
      (node (ref "C3") (pin "1") (pinfunction "1_1") (pintype "passive"))
      (node (ref "R") (pin "TP") (pinfunction "TP_TP") (pintype "input"))
      (node (ref "R3") (pin "1") (pinfunction "1_1") (pintype "passive"))
    )
    (net (code "53") (name "R_STR") (class "Default")
      (node (ref "R3") (pin "2") (pinfunction "2_2") (pintype "passive"))
      (node (ref "STEERING") (pin "4") (pinfunction "4_4") (pintype "passive"))
    )
    (net (code "54") (name "SCK") (class "Default")
      (node (ref "IC1_2515") (pin "13") (pinfunction "SCK_13") (pintype "input"))
      (node (ref "IC3_4802") (pin "3") (pinfunction "3_3") (pintype "passive"))
      (node (ref "ICSP") (pin "3") (pinfunction "3_3") (pintype "passive"))
      (node (ref "MEGA_EXPANSION") (pin "4") (pinfunction "4_4") (pintype "passive"))
    )
    (net (code "55") (name "SOLENOID_COMMON") (class "Default")
      (node (ref "D1") (pin "A") (pinfunction "A_A") (pintype "passive"))
      (node (ref "PB1_BRAKE_ON") (pin "5") (pinfunction "NO_5") (pintype "passive"))
      (node (ref "X1") (pin "1") (pinfunction "1_1") (pintype "passive"))
    )
    (net (code "56") (name "SOLENOID_OUT") (class "Default")
      (node (ref "D1") (pin "C") (pinfunction "C_C") (pintype "passive"))
      (node (ref "PB1_BRAKE_ON") (pin "3") (pinfunction "C_3") (pintype "passive"))
      (node (ref "X1") (pin "2") (pinfunction "2_2") (pintype "passive"))
    )
    (net (code "57") (name "SOLENOID_POWER") (class "Default")
      (node (ref "PB1_BRAKE_ON") (pin "4") (pinfunction "NC_4") (pintype "passive"))
      (node (ref "PB2_12/24") (pin "3") (pinfunction "C_3") (pintype "passive"))
    )
    (net (code "58") (name "SPEEDOMETER") (class "Default")
      (node (ref "ADCH") (pin "5") (pinfunction "5_5") (pintype "passive"))
      (node (ref "X3") (pin "14") (pinfunction "14_14") (pintype "passive"))
    )
    (net (code "59") (name "SPI_SLAVE") (class "Default")
      (node (ref "MEGA_EXPANSION") (pin "3") (pinfunction "3_3") (pintype "passive"))
    )
    (net (code "60") (name "STEER_SERVO_PWM") (class "Default")
      (node (ref "DIGITAL_0-7") (pin "7") (pinfunction "7_7") (pintype "passive"))
      (node (ref "STEER") (pin "TP") (pinfunction "TP_TP") (pintype "input"))
      (node (ref "STEERING") (pin "6") (pinfunction "6_6") (pintype "passive"))
    )
    (net (code "61") (name "TX0") (class "Default")
      (node (ref "DIGITAL_0-7") (pin "2") (pinfunction "2_2") (pintype "passive"))
    )
    (net (code "62") (name "TX3") (class "Default")
      (node (ref "CAN/UART") (pin "6") (pinfunction "6_6") (pintype "passive"))
      (node (ref "DIGITAL_14-21") (pin "8") (pinfunction "8_8") (pintype "passive"))
    )
    (net (code "63") (name "VIN") (class "Default")
      (node (ref "POWER") (pin "6") (pinfunction "6_6") (pintype "passive"))
    )
    (net (code "64") (name "VOLTAGE_SWITCH") (class "Default")
      (node (ref "MEGA_EXPANSION") (pin "19") (pinfunction "19_19") (pintype "passive"))
      (node (ref "R5") (pin "1") (pinfunction "1_1") (pintype "passive"))
    )
    (net (code "65") (name "WHEELROTATION") (class "Default")
      (node (ref "ADCH") (pin "8") (pinfunction "8_8") (pintype "passive"))
      (node (ref "C9") (pin "1") (pinfunction "1_1") (pintype "passive"))
      (node (ref "R17") (pin "2") (pinfunction "2_2") (pintype "passive"))
      (node (ref "X4") (pin "P$1") (pinfunction "1_P$1") (pintype "passive"))
    )
    (net (code "66") (name "unconnected-(ADCL-Pad1)") (class "Default")
      (node (ref "ADCL") (pin "1") (pinfunction "1_1") (pintype "passive"))
    )
    (net (code "67") (name "unconnected-(ADCL-Pad2)") (class "Default")
      (node (ref "ADCL") (pin "2") (pinfunction "2_2") (pintype "passive"))
    )
    (net (code "68") (name "unconnected-(ADCL-Pad3)") (class "Default")
      (node (ref "ADCL") (pin "3") (pinfunction "3_3") (pintype "passive"))
    )
    (net (code "69") (name "unconnected-(ADCL-Pad4)") (class "Default")
      (node (ref "ADCL") (pin "4") (pinfunction "4_4") (pintype "passive"))
    )
    (net (code "70") (name "unconnected-(ADCL-Pad7)") (class "Default")
      (node (ref "ADCL") (pin "7") (pinfunction "7_7") (pintype "passive"))
    )
    (net (code "71") (name "unconnected-(ADCL-Pad8)") (class "Default")
      (node (ref "ADCL") (pin "8") (pinfunction "8_8") (pintype "passive"))
    )
    (net (code "72") (name "unconnected-(CAN/UART-Pad4)") (class "Default")
      (node (ref "CAN/UART") (pin "4") (pinfunction "4_4") (pintype "passive"))
    )
    (net (code "73") (name "unconnected-(CAN/UART-Pad5)") (class "Default")
      (node (ref "CAN/UART") (pin "5") (pinfunction "5_5") (pintype "passive"))
    )
    (net (code "74") (name "unconnected-(CAN/UART-Pad9)") (class "Default")
      (node (ref "CAN/UART") (pin "9") (pinfunction "9_9") (pintype "passive"))
    )
    (net (code "75") (name "unconnected-(DIGITAL_0-7-Pad4)") (class "Default")
      (node (ref "DIGITAL_0-7") (pin "4") (pinfunction "4_4") (pintype "passive"))
    )
    (net (code "76") (name "unconnected-(DIGITAL_0-7-Pad5)") (class "Default")
      (node (ref "DIGITAL_0-7") (pin "5") (pinfunction "5_5") (pintype "passive"))
    )
    (net (code "77") (name "unconnected-(DIGITAL_0-7-Pad6)") (class "Default")
      (node (ref "DIGITAL_0-7") (pin "6") (pinfunction "6_6") (pintype "passive"))
    )
    (net (code "78") (name "unconnected-(DIGITAL_0-7-Pad8)") (class "Default")
      (node (ref "DIGITAL_0-7") (pin "8") (pinfunction "8_8") (pintype "passive"))
    )
    (net (code "79") (name "unconnected-(DIGITAL_8-13-Pad1)") (class "Default")
      (node (ref "DIGITAL_8-13") (pin "1") (pinfunction "1_1") (pintype "passive"))
    )
    (net (code "80") (name "unconnected-(DIGITAL_8-13-Pad2)") (class "Default")
      (node (ref "DIGITAL_8-13") (pin "2") (pinfunction "2_2") (pintype "passive"))
    )
    (net (code "81") (name "unconnected-(DIGITAL_8-13-Pad3)") (class "Default")
      (node (ref "DIGITAL_8-13") (pin "3") (pinfunction "3_3") (pintype "passive"))
    )
    (net (code "82") (name "unconnected-(DIGITAL_8-13-Pad4)") (class "Default")
      (node (ref "DIGITAL_8-13") (pin "4") (pinfunction "4_4") (pintype "passive"))
    )
    (net (code "83") (name "unconnected-(DIGITAL_8-13-Pad5)") (class "Default")
      (node (ref "DIGITAL_8-13") (pin "5") (pinfunction "5_5") (pintype "passive"))
    )
    (net (code "84") (name "unconnected-(DIGITAL_8-13-Pad8)") (class "Default")
      (node (ref "DIGITAL_8-13") (pin "8") (pinfunction "8_8") (pintype "passive"))
    )
    (net (code "85") (name "unconnected-(DIGITAL_8-13-Pad9)") (class "Default")
      (node (ref "DIGITAL_8-13") (pin "9") (pinfunction "9_9") (pintype "passive"))
    )
    (net (code "86") (name "unconnected-(DIGITAL_8-13-Pad10)") (class "Default")
      (node (ref "DIGITAL_8-13") (pin "10") (pinfunction "10_10") (pintype "passive"))
    )
    (net (code "87") (name "unconnected-(DIGITAL_14-21-Pad1)") (class "Default")
      (node (ref "DIGITAL_14-21") (pin "1") (pinfunction "1_1") (pintype "passive"))
    )
    (net (code "88") (name "unconnected-(DIGITAL_14-21-Pad2)") (class "Default")
      (node (ref "DIGITAL_14-21") (pin "2") (pinfunction "2_2") (pintype "passive"))
    )
    (net (code "89") (name "unconnected-(DIGITAL_14-21-Pad3)") (class "Default")
      (node (ref "DIGITAL_14-21") (pin "3") (pinfunction "3_3") (pintype "passive"))
    )
    (net (code "90") (name "unconnected-(DIGITAL_14-21-Pad4)") (class "Default")
      (node (ref "DIGITAL_14-21") (pin "4") (pinfunction "4_4") (pintype "passive"))
    )
    (net (code "91") (name "unconnected-(DIGITAL_14-21-Pad5)") (class "Default")
      (node (ref "DIGITAL_14-21") (pin "5") (pinfunction "5_5") (pintype "passive"))
    )
    (net (code "92") (name "unconnected-(DIGITAL_14-21-Pad6)") (class "Default")
      (node (ref "DIGITAL_14-21") (pin "6") (pinfunction "6_6") (pintype "passive"))
    )
    (net (code "93") (name "unconnected-(IC1_2515A-CLKOUT-Pad3)") (class "Default")
      (node (ref "IC1_2515") (pin "3") (pinfunction "CLKOUT_3") (pintype "output"))
    )
    (net (code "94") (name "unconnected-(IC1_2515A-RX0BF-Pad11)") (class "Default")
      (node (ref "IC1_2515") (pin "11") (pinfunction "RX0BF_11") (pintype "output"))
    )
    (net (code "95") (name "unconnected-(IC1_2515A-RX1BF-Pad10)") (class "Default")
      (node (ref "IC1_2515") (pin "10") (pinfunction "RX1BF_10") (pintype "output"))
    )
    (net (code "96") (name "unconnected-(IC2_2551-VREF-Pad5)") (class "Default")
      (node (ref "IC2_2551") (pin "5") (pinfunction "VREF_5") (pintype "bidirectional"))
    )
    (net (code "97") (name "unconnected-(MEGA_EXPANSION-Pad9)") (class "Default")
      (node (ref "MEGA_EXPANSION") (pin "9") (pinfunction "9_9") (pintype "passive"))
    )
    (net (code "98") (name "unconnected-(MEGA_EXPANSION-Pad10)") (class "Default")
      (node (ref "MEGA_EXPANSION") (pin "10") (pinfunction "10_10") (pintype "passive"))
    )
    (net (code "99") (name "unconnected-(MEGA_EXPANSION-Pad11)") (class "Default")
      (node (ref "MEGA_EXPANSION") (pin "11") (pinfunction "11_11") (pintype "passive"))
    )
    (net (code "100") (name "unconnected-(MEGA_EXPANSION-Pad12)") (class "Default")
      (node (ref "MEGA_EXPANSION") (pin "12") (pinfunction "12_12") (pintype "passive"))
    )
    (net (code "101") (name "unconnected-(MEGA_EXPANSION-Pad13)") (class "Default")
      (node (ref "MEGA_EXPANSION") (pin "13") (pinfunction "13_13") (pintype "passive"))
    )
    (net (code "102") (name "unconnected-(MEGA_EXPANSION-Pad14)") (class "Default")
      (node (ref "MEGA_EXPANSION") (pin "14") (pinfunction "14_14") (pintype "passive"))
    )
    (net (code "103") (name "unconnected-(MEGA_EXPANSION-Pad15)") (class "Default")
      (node (ref "MEGA_EXPANSION") (pin "15") (pinfunction "15_15") (pintype "passive"))
    )
    (net (code "104") (name "unconnected-(MEGA_EXPANSION-Pad16)") (class "Default")
      (node (ref "MEGA_EXPANSION") (pin "16") (pinfunction "16_16") (pintype "passive"))
    )
    (net (code "105") (name "unconnected-(MEGA_EXPANSION-Pad21)") (class "Default")
      (node (ref "MEGA_EXPANSION") (pin "21") (pinfunction "21_21") (pintype "passive"))
    )
    (net (code "106") (name "unconnected-(MEGA_EXPANSION-Pad23)") (class "Default")
      (node (ref "MEGA_EXPANSION") (pin "23") (pinfunction "23_23") (pintype "passive"))
    )
    (net (code "107") (name "unconnected-(MEGA_EXPANSION-Pad24)") (class "Default")
      (node (ref "MEGA_EXPANSION") (pin "24") (pinfunction "24_24") (pintype "passive"))
    )
    (net (code "108") (name "unconnected-(MEGA_EXPANSION-Pad25)") (class "Default")
      (node (ref "MEGA_EXPANSION") (pin "25") (pinfunction "25_25") (pintype "passive"))
    )
    (net (code "109") (name "unconnected-(MEGA_EXPANSION-Pad26)") (class "Default")
      (node (ref "MEGA_EXPANSION") (pin "26") (pinfunction "26_26") (pintype "passive"))
    )
    (net (code "110") (name "unconnected-(MEGA_EXPANSION-Pad27)") (class "Default")
      (node (ref "MEGA_EXPANSION") (pin "27") (pinfunction "27_27") (pintype "passive"))
    )
    (net (code "111") (name "unconnected-(MEGA_EXPANSION-Pad28)") (class "Default")
      (node (ref "MEGA_EXPANSION") (pin "28") (pinfunction "28_28") (pintype "passive"))
    )
    (net (code "112") (name "unconnected-(MEGA_EXPANSION-Pad29)") (class "Default")
      (node (ref "MEGA_EXPANSION") (pin "29") (pinfunction "29_29") (pintype "passive"))
    )
    (net (code "113") (name "unconnected-(MEGA_EXPANSION-Pad30)") (class "Default")
      (node (ref "MEGA_EXPANSION") (pin "30") (pinfunction "30_30") (pintype "passive"))
    )
    (net (code "114") (name "unconnected-(MEGA_EXPANSION-Pad31)") (class "Default")
      (node (ref "MEGA_EXPANSION") (pin "31") (pinfunction "31_31") (pintype "passive"))
    )
    (net (code "115") (name "unconnected-(MEGA_EXPANSION-Pad33)") (class "Default")
      (node (ref "MEGA_EXPANSION") (pin "33") (pinfunction "33_33") (pintype "passive"))
    )
    (net (code "116") (name "unconnected-(X3-Pad13)") (class "Default")
      (node (ref "X3") (pin "13") (pinfunction "13_13") (pintype "passive"))
    )
  )
)
